# 8_Port.net
KiCad netlist of a schematic drawn in Altium Designer
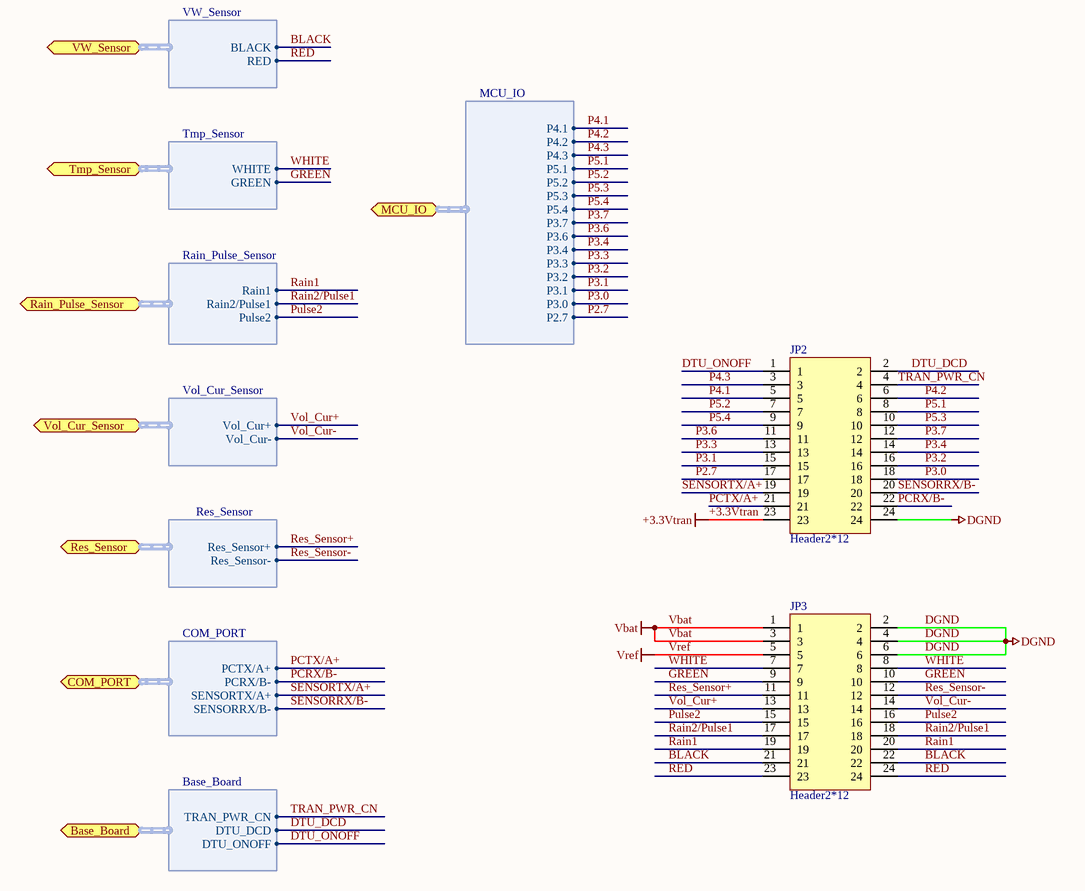
[diagram p0: 8_Port.SchDoc]

(export (version "E")
  (design (tool "Eeschema 10.0.6"))
  (components
    (comp (ref "JP2")
      (value "Header2*12")
      (footprint "IDC24-2.0MM-INSERT")
      (libsource (lib "Connector") (part "Header2*12"))
    )
    (comp (ref "JP3")
      (value "Header2*12")
      (footprint "IDC24-2.0MM-INSERT")
      (libsource (lib "Connector") (part "Header2*12"))
    )
  )
  (nets
    (net (code "9") (name "+3.3Vtran") (class "Default")
      (node (ref "JP2") (pin "23") (pinfunction "23_23") (pintype "passive"))
    )
    (net (code "10") (name "/BLACK") (class "Default")
      (node (ref "JP3") (pin "21") (pinfunction "21_21") (pintype "passive"))
      (node (ref "JP3") (pin "22") (pinfunction "22_22") (pintype "passive"))
    )
    (net (code "11") (name "/DTU_DCD") (class "Default")
      (node (ref "JP2") (pin "2") (pinfunction "2_2") (pintype "passive"))
    )
    (net (code "12") (name "/DTU_ONOFF") (class "Default")
      (node (ref "JP2") (pin "1") (pinfunction "1_1") (pintype "passive"))
    )
    (net (code "13") (name "/GREEN") (class "Default")
      (node (ref "JP3") (pin "10") (pinfunction "10_10") (pintype "passive"))
      (node (ref "JP3") (pin "9") (pinfunction "9_9") (pintype "passive"))
    )
    (net (code "14") (name "/P2.7") (class "Default")
      (node (ref "JP2") (pin "17") (pinfunction "17_17") (pintype "passive"))
    )
    (net (code "15") (name "/P3.0") (class "Default")
      (node (ref "JP2") (pin "18") (pinfunction "18_18") (pintype "passive"))
    )
    (net (code "16") (name "/P3.1") (class "Default")
      (node (ref "JP2") (pin "15") (pinfunction "15_15") (pintype "passive"))
    )
    (net (code "17") (name "/P3.2") (class "Default")
      (node (ref "JP2") (pin "16") (pinfunction "16_16") (pintype "passive"))
    )
    (net (code "18") (name "/P3.3") (class "Default")
      (node (ref "JP2") (pin "13") (pinfunction "13_13") (pintype "passive"))
    )
    (net (code "19") (name "/P3.4") (class "Default")
      (node (ref "JP2") (pin "14") (pinfunction "14_14") (pintype "passive"))
    )
    (net (code "20") (name "/P3.6") (class "Default")
      (node (ref "JP2") (pin "11") (pinfunction "11_11") (pintype "passive"))
    )
    (net (code "21") (name "/P3.7") (class "Default")
      (node (ref "JP2") (pin "12") (pinfunction "12_12") (pintype "passive"))
    )
    (net (code "22") (name "/P4.1") (class "Default")
      (node (ref "JP2") (pin "5") (pinfunction "5_5") (pintype "passive"))
    )
    (net (code "23") (name "/P4.2") (class "Default")
      (node (ref "JP2") (pin "6") (pinfunction "6_6") (pintype "passive"))
    )
    (net (code "24") (name "/P4.3") (class "Default")
      (node (ref "JP2") (pin "3") (pinfunction "3_3") (pintype "passive"))
    )
    (net (code "25") (name "/P5.1") (class "Default")
      (node (ref "JP2") (pin "8") (pinfunction "8_8") (pintype "passive"))
    )
    (net (code "26") (name "/P5.2") (class "Default")
      (node (ref "JP2") (pin "7") (pinfunction "7_7") (pintype "passive"))
    )
    (net (code "27") (name "/P5.3") (class "Default")
      (node (ref "JP2") (pin "10") (pinfunction "10_10") (pintype "passive"))
    )
    (net (code "28") (name "/P5.4") (class "Default")
      (node (ref "JP2") (pin "9") (pinfunction "9_9") (pintype "passive"))
    )
    (net (code "29") (name "/PCRX{slash}B-") (class "Default")
      (node (ref "JP2") (pin "22") (pinfunction "22_22") (pintype "passive"))
    )
    (net (code "30") (name "/PCTX{slash}A+") (class "Default")
      (node (ref "JP2") (pin "21") (pinfunction "21_21") (pintype "passive"))
    )
    (net (code "31") (name "/Pulse2") (class "Default")
      (node (ref "JP3") (pin "15") (pinfunction "15_15") (pintype "passive"))
      (node (ref "JP3") (pin "16") (pinfunction "16_16") (pintype "passive"))
    )
    (net (code "32") (name "/RED") (class "Default")
      (node (ref "JP3") (pin "23") (pinfunction "23_23") (pintype "passive"))
      (node (ref "JP3") (pin "24") (pinfunction "24_24") (pintype "passive"))
    )
    (net (code "33") (name "/Rain1") (class "Default")
      (node (ref "JP3") (pin "19") (pinfunction "19_19") (pintype "passive"))
      (node (ref "JP3") (pin "20") (pinfunction "20_20") (pintype "passive"))
    )
    (net (code "34") (name "/Rain2{slash}Pulse1") (class "Default")
      (node (ref "JP3") (pin "17") (pinfunction "17_17") (pintype "passive"))
      (node (ref "JP3") (pin "18") (pinfunction "18_18") (pintype "passive"))
    )
    (net (code "35") (name "/Res_Sensor+") (class "Default")
      (node (ref "JP3") (pin "11") (pinfunction "11_11") (pintype "passive"))
    )
    (net (code "36") (name "/Res_Sensor-") (class "Default")
      (node (ref "JP3") (pin "12") (pinfunction "12_12") (pintype "passive"))
    )
    (net (code "37") (name "/SENSORRX{slash}B-") (class "Default")
      (node (ref "JP2") (pin "20") (pinfunction "20_20") (pintype "passive"))
    )
    (net (code "38") (name "/SENSORTX{slash}A+") (class "Default")
      (node (ref "JP2") (pin "19") (pinfunction "19_19") (pintype "passive"))
    )
    (net (code "39") (name "/TRAN_PWR_CN") (class "Default")
      (node (ref "JP2") (pin "4") (pinfunction "4_4") (pintype "passive"))
    )
    (net (code "40") (name "/Vol_Cur+") (class "Default")
      (node (ref "JP3") (pin "13") (pinfunction "13_13") (pintype "passive"))
    )
    (net (code "41") (name "/Vol_Cur-") (class "Default")
      (node (ref "JP3") (pin "14") (pinfunction "14_14") (pintype "passive"))
    )
    (net (code "42") (name "/WHITE") (class "Default")
      (node (ref "JP3") (pin "7") (pinfunction "7_7") (pintype "passive"))
      (node (ref "JP3") (pin "8") (pinfunction "8_8") (pintype "passive"))
    )
    (net (code "51") (name "DGND") (class "Default")
      (node (ref "JP2") (pin "24") (pinfunction "24_24") (pintype "passive"))
      (node (ref "JP3") (pin "2") (pinfunction "2_2") (pintype "passive"))
      (node (ref "JP3") (pin "4") (pinfunction "4_4") (pintype "passive"))
      (node (ref "JP3") (pin "6") (pinfunction "6_6") (pintype "passive"))
    )
    (net (code "52") (name "Vbat") (class "Default")
      (node (ref "JP3") (pin "1") (pinfunction "1_1") (pintype "passive"))
      (node (ref "JP3") (pin "3") (pinfunction "3_3") (pintype "passive"))
    )
    (net (code "53") (name "Vref") (class "Default")
      (node (ref "JP3") (pin "5") (pinfunction "5_5") (pintype "passive"))
    )
  )
)
